# E-08_eMMC.net
KiCad netlist of a schematic drawn in Altium Designer
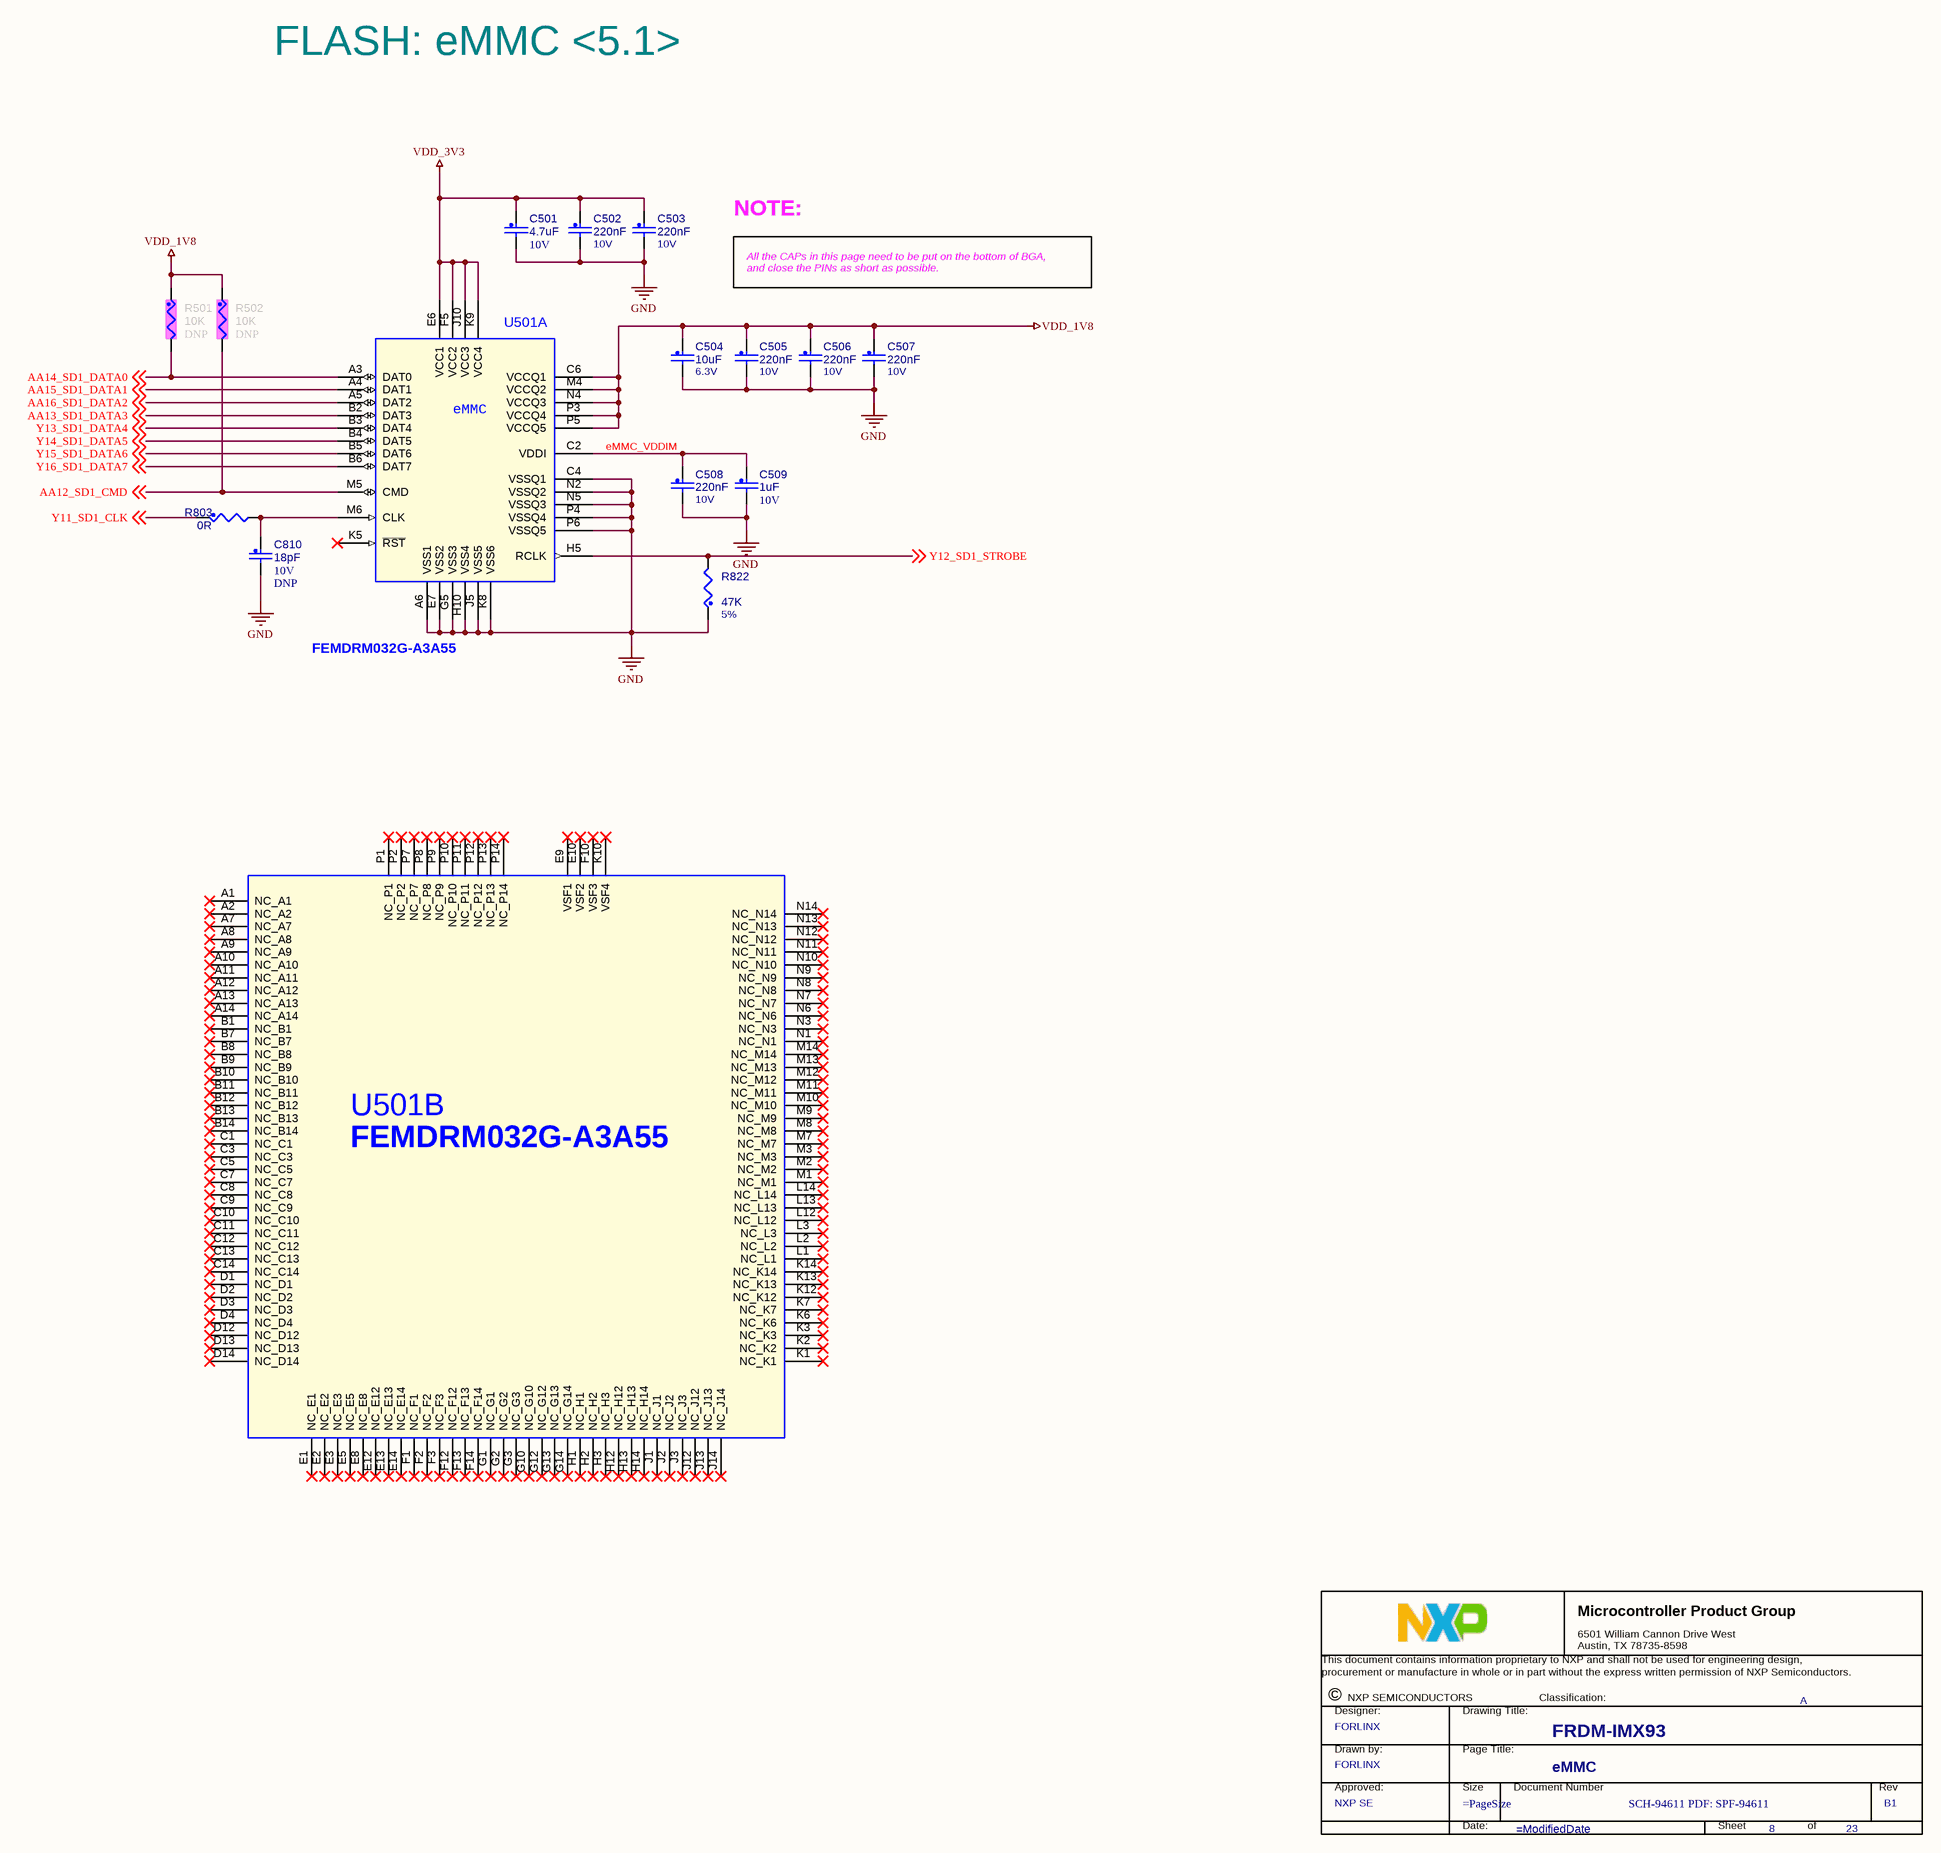
[diagram p0: E-08 eMMC.SchDoc]

(export (version "E")
  (design (tool "Eeschema 10.0.6"))
  (components
    (comp (ref "C501")
      (value "4.7uF")
      (footprint "C0402")
      (description "0402,4.7uF,10V,+/-10%,X5R")
      (fields (field (name "VOLTAGE") "10V") (field (name "TOLERANCE") "10%"))
      (libsource (lib "*") (part "CAP_NP"))
    )
    (comp (ref "C502")
      (value "220nF")
      (footprint "C0201")
      (description "0201,220nF,6.3V,+/-20%,X5R")
      (fields (field (name "TOLERANCE") "20%") (field (name "VOLTAGE") "10V"))
      (libsource (lib "*") (part "CAP_NP"))
    )
    (comp (ref "C503")
      (value "220nF")
      (footprint "C0201")
      (description "0201,220nF,6.3V,+/-20%,X5R")
      (fields (field (name "VOLTAGE") "10V") (field (name "TOLERANCE") "20%"))
      (libsource (lib "*") (part "CAP_NP"))
    )
    (comp (ref "C504")
      (value "10uF")
      (footprint "C0402")
      (description "0402,10uF,6.3V,+/-20%,X5R")
      (fields (field (name "VOLTAGE") "6.3V") (field (name "TOLERANCE") "20%"))
      (libsource (lib "*") (part "CAP_NP"))
    )
    (comp (ref "C505")
      (value "220nF")
      (footprint "C0201")
      (description "0201,220nF,6.3V,+/-20%,X5R")
      (fields (field (name "VOLTAGE") "10V") (field (name "TOLERANCE") "20%"))
      (libsource (lib "*") (part "CAP_NP"))
    )
    (comp (ref "C506")
      (value "220nF")
      (footprint "C0201")
      (description "0201,220nF,6.3V,+/-20%,X5R")
      (fields (field (name "VOLTAGE") "10V") (field (name "TOLERANCE") "20%"))
      (libsource (lib "*") (part "CAP_NP"))
    )
    (comp (ref "C507")
      (value "220nF")
      (footprint "C0201")
      (description "0201,220nF,6.3V,+/-20%,X5R")
      (fields (field (name "TOLERANCE") "20%") (field (name "VOLTAGE") "10V"))
      (libsource (lib "*") (part "CAP_NP"))
    )
    (comp (ref "C508")
      (value "220nF")
      (footprint "C0201")
      (description "0201,220nF,6.3V,+/-20%,X5R")
      (fields (field (name "TOLERANCE") "20%") (field (name "VOLTAGE") "10V"))
      (libsource (lib "*") (part "CAP_NP"))
    )
    (comp (ref "C509")
      (value "1uF")
      (footprint "C0201")
      (description "0201,1uF,10V,+/-20%,X5R")
      (fields (field (name "VOLTAGE") "10V") (field (name "TOLERANCE") "10%"))
      (libsource (lib "*") (part "CAP_NP"))
    )
    (comp (ref "C810")
      (value "18pF")
      (footprint "C0201")
      (description "0201,18pF,50V,+/-5%,NPO")
      (fields (field (name "ASSY_OPT") "DNP") (field (name "VOLTAGE") "10V") (field (name "TOLERANCE") "10%"))
      (libsource (lib "*") (part "CAP_NP"))
    )
    (comp (ref "R501")
      (value "10K")
      (footprint "R0201")
      (description "0201,10K,+/-5%")
      (fields (field (name "ASSY_OPT") "DNP") (field (name "TOLERANCE") "5%"))
      (libsource (lib "*") (part "RES"))
    )
    (comp (ref "R502")
      (value "10K")
      (footprint "R0201")
      (description "0201,10K,+/-5%")
      (fields (field (name "ASSY_OPT") "DNP") (field (name "TOLERANCE") "5%"))
      (libsource (lib "*") (part "RES"))
    )
    (comp (ref "R803")
      (value "0R")
      (footprint "R0201")
      (description "0201,0Ohm,+/-5%")
      (fields (field (name "TOLERANCE") "5%"))
      (libsource (lib "*") (part "RES"))
    )
    (comp (ref "R822")
      (value "47K")
      (footprint "R0201")
      (description "0201,47K,5%")
      (fields (field (name "TOLERANCE") "5%") (field (name "VOLTAGE") "25V"))
      (libsource (lib "*") (part "RES"))
    )
    (comp (ref "U501")
      (value "FEMDRM032G-A3A55")
      (footprint "fbga153_0p5_11p5x13")
      (description "FEMDRM032G-A3A55,153FBGA,eMMC5.1,32GB,-25~85+C")
      (libsource (lib "*") (part "SDINBDA6_32G_I_VFBGA_153P"))
    )
  )
  (nets
    (net (code "1") (name "/eMMC_VDDIM") (class "Default")
      (node (ref "C508") (pin "1") (pinfunction "1_1") (pintype "passive"))
      (node (ref "C509") (pin "1") (pinfunction "1_1") (pintype "passive"))
      (node (ref "U501") (pin "C2") (pinfunction "VDDI_C2") (pintype "power_in"))
    )
    (net (code "2") (name "AA12_SD1_CMD") (class "Default")
      (node (ref "R502") (pin "2") (pinfunction "2_2") (pintype "passive"))
      (node (ref "U501") (pin "M5") (pinfunction "CMD_M5") (pintype "bidirectional"))
    )
    (net (code "3") (name "AA13_SD1_DATA3") (class "Default")
      (node (ref "U501") (pin "B2") (pinfunction "DAT3_B2") (pintype "bidirectional"))
    )
    (net (code "4") (name "AA14_SD1_DATA0") (class "Default")
      (node (ref "R501") (pin "2") (pinfunction "2_2") (pintype "passive"))
      (node (ref "U501") (pin "A3") (pinfunction "DAT0_A3") (pintype "bidirectional"))
    )
    (net (code "5") (name "AA15_SD1_DATA1") (class "Default")
      (node (ref "U501") (pin "A4") (pinfunction "DAT1_A4") (pintype "bidirectional"))
    )
    (net (code "6") (name "AA16_SD1_DATA2") (class "Default")
      (node (ref "U501") (pin "A5") (pinfunction "DAT2_A5") (pintype "bidirectional"))
    )
    (net (code "7") (name "GND") (class "Default")
      (node (ref "C501") (pin "2") (pinfunction "2_2") (pintype "passive"))
      (node (ref "C502") (pin "2") (pinfunction "2_2") (pintype "passive"))
      (node (ref "C503") (pin "2") (pinfunction "2_2") (pintype "passive"))
      (node (ref "C504") (pin "2") (pinfunction "2_2") (pintype "passive"))
      (node (ref "C505") (pin "2") (pinfunction "2_2") (pintype "passive"))
      (node (ref "C506") (pin "2") (pinfunction "2_2") (pintype "passive"))
      (node (ref "C507") (pin "2") (pinfunction "2_2") (pintype "passive"))
      (node (ref "C508") (pin "2") (pinfunction "2_2") (pintype "passive"))
      (node (ref "C509") (pin "2") (pinfunction "2_2") (pintype "passive"))
      (node (ref "C810") (pin "2") (pinfunction "2_2") (pintype "passive"))
      (node (ref "R822") (pin "1") (pinfunction "1_1") (pintype "passive"))
      (node (ref "U501") (pin "A6") (pinfunction "VSS1_A6") (pintype "power_in"))
      (node (ref "U501") (pin "C4") (pinfunction "VSSQ1_C4") (pintype "power_in"))
      (node (ref "U501") (pin "E7") (pinfunction "VSS2_E7") (pintype "power_in"))
      (node (ref "U501") (pin "G5") (pinfunction "VSS3_G5") (pintype "power_in"))
      (node (ref "U501") (pin "H10") (pinfunction "VSS4_H10") (pintype "power_in"))
      (node (ref "U501") (pin "J5") (pinfunction "VSS5_J5") (pintype "power_in"))
      (node (ref "U501") (pin "K8") (pinfunction "VSS6_K8") (pintype "power_in"))
      (node (ref "U501") (pin "N2") (pinfunction "VSSQ2_N2") (pintype "power_in"))
      (node (ref "U501") (pin "N5") (pinfunction "VSSQ3_N5") (pintype "power_in"))
      (node (ref "U501") (pin "P4") (pinfunction "VSSQ4_P4") (pintype "power_in"))
      (node (ref "U501") (pin "P6") (pinfunction "VSSQ5_P6") (pintype "power_in"))
    )
    (net (code "8") (name "Net-(U501A-CLK)") (class "Default")
      (node (ref "C810") (pin "1") (pinfunction "1_1") (pintype "passive"))
      (node (ref "R803") (pin "2") (pinfunction "2_2") (pintype "passive"))
      (node (ref "U501") (pin "M6") (pinfunction "CLK_M6") (pintype "input"))
    )
    (net (code "9") (name "VDD_1V8") (class "Default")
      (node (ref "C504") (pin "1") (pinfunction "1_1") (pintype "passive"))
      (node (ref "C505") (pin "1") (pinfunction "1_1") (pintype "passive"))
      (node (ref "C506") (pin "1") (pinfunction "1_1") (pintype "passive"))
      (node (ref "C507") (pin "1") (pinfunction "1_1") (pintype "passive"))
      (node (ref "R501") (pin "1") (pinfunction "1_1") (pintype "passive"))
      (node (ref "R502") (pin "1") (pinfunction "1_1") (pintype "passive"))
      (node (ref "U501") (pin "C6") (pinfunction "VCCQ1_C6") (pintype "power_in"))
      (node (ref "U501") (pin "M4") (pinfunction "VCCQ2_M4") (pintype "power_in"))
      (node (ref "U501") (pin "N4") (pinfunction "VCCQ3_N4") (pintype "power_in"))
      (node (ref "U501") (pin "P3") (pinfunction "VCCQ4_P3") (pintype "power_in"))
      (node (ref "U501") (pin "P5") (pinfunction "VCCQ5_P5") (pintype "power_in"))
    )
    (net (code "10") (name "VDD_3V3") (class "Default")
      (node (ref "C501") (pin "1") (pinfunction "1_1") (pintype "passive"))
      (node (ref "C502") (pin "1") (pinfunction "1_1") (pintype "passive"))
      (node (ref "C503") (pin "1") (pinfunction "1_1") (pintype "passive"))
      (node (ref "U501") (pin "E6") (pinfunction "VCC1_E6") (pintype "power_in"))
      (node (ref "U501") (pin "F5") (pinfunction "VCC2_F5") (pintype "power_in"))
      (node (ref "U501") (pin "J10") (pinfunction "VCC3_J10") (pintype "power_in"))
      (node (ref "U501") (pin "K9") (pinfunction "VCC4_K9") (pintype "power_in"))
    )
    (net (code "11") (name "Y11_SD1_CLK") (class "Default")
      (node (ref "R803") (pin "1") (pinfunction "1_1") (pintype "passive"))
    )
    (net (code "12") (name "Y12_SD1_STROBE") (class "Default")
      (node (ref "R822") (pin "2") (pinfunction "2_2") (pintype "passive"))
      (node (ref "U501") (pin "H5") (pinfunction "RCLK_H5") (pintype "output"))
    )
    (net (code "13") (name "Y13_SD1_DATA4") (class "Default")
      (node (ref "U501") (pin "B3") (pinfunction "DAT4_B3") (pintype "bidirectional"))
    )
    (net (code "14") (name "Y14_SD1_DATA5") (class "Default")
      (node (ref "U501") (pin "B4") (pinfunction "DAT5_B4") (pintype "bidirectional"))
    )
    (net (code "15") (name "Y15_SD1_DATA6") (class "Default")
      (node (ref "U501") (pin "B5") (pinfunction "DAT6_B5") (pintype "bidirectional"))
    )
    (net (code "16") (name "Y16_SD1_DATA7") (class "Default")
      (node (ref "U501") (pin "B6") (pinfunction "DAT7_B6") (pintype "bidirectional"))
    )
    (net (code "17") (name "unconnected-(U501A-~{RST}-PadK5)") (class "Default")
      (node (ref "U501") (pin "K5") (pinfunction "~{RST}_K5") (pintype "input+no_connect"))
    )
    (net (code "18") (name "unconnected-(U501B-NC_A1-PadA1)") (class "Default")
      (node (ref "U501") (pin "A1") (pinfunction "NC_A1_A1") (pintype "passive+no_connect"))
    )
    (net (code "19") (name "unconnected-(U501B-NC_A2-PadA2)") (class "Default")
      (node (ref "U501") (pin "A2") (pinfunction "NC_A2_A2") (pintype "passive+no_connect"))
    )
    (net (code "20") (name "unconnected-(U501B-NC_A7-PadA7)") (class "Default")
      (node (ref "U501") (pin "A7") (pinfunction "NC_A7_A7") (pintype "passive+no_connect"))
    )
    (net (code "21") (name "unconnected-(U501B-NC_A8-PadA8)") (class "Default")
      (node (ref "U501") (pin "A8") (pinfunction "NC_A8_A8") (pintype "passive+no_connect"))
    )
    (net (code "22") (name "unconnected-(U501B-NC_A9-PadA9)") (class "Default")
      (node (ref "U501") (pin "A9") (pinfunction "NC_A9_A9") (pintype "passive+no_connect"))
    )
    (net (code "23") (name "unconnected-(U501B-NC_A10-PadA10)") (class "Default")
      (node (ref "U501") (pin "A10") (pinfunction "NC_A10_A10") (pintype "passive+no_connect"))
    )
    (net (code "24") (name "unconnected-(U501B-NC_A11-PadA11)") (class "Default")
      (node (ref "U501") (pin "A11") (pinfunction "NC_A11_A11") (pintype "passive+no_connect"))
    )
    (net (code "25") (name "unconnected-(U501B-NC_A12-PadA12)") (class "Default")
      (node (ref "U501") (pin "A12") (pinfunction "NC_A12_A12") (pintype "passive+no_connect"))
    )
    (net (code "26") (name "unconnected-(U501B-NC_A13-PadA13)") (class "Default")
      (node (ref "U501") (pin "A13") (pinfunction "NC_A13_A13") (pintype "passive+no_connect"))
    )
    (net (code "27") (name "unconnected-(U501B-NC_A14-PadA14)") (class "Default")
      (node (ref "U501") (pin "A14") (pinfunction "NC_A14_A14") (pintype "passive+no_connect"))
    )
    (net (code "28") (name "unconnected-(U501B-NC_B1-PadB1)") (class "Default")
      (node (ref "U501") (pin "B1") (pinfunction "NC_B1_B1") (pintype "passive+no_connect"))
    )
    (net (code "29") (name "unconnected-(U501B-NC_B7-PadB7)") (class "Default")
      (node (ref "U501") (pin "B7") (pinfunction "NC_B7_B7") (pintype "passive+no_connect"))
    )
    (net (code "30") (name "unconnected-(U501B-NC_B8-PadB8)") (class "Default")
      (node (ref "U501") (pin "B8") (pinfunction "NC_B8_B8") (pintype "passive+no_connect"))
    )
    (net (code "31") (name "unconnected-(U501B-NC_B9-PadB9)") (class "Default")
      (node (ref "U501") (pin "B9") (pinfunction "NC_B9_B9") (pintype "passive+no_connect"))
    )
    (net (code "32") (name "unconnected-(U501B-NC_B10-PadB10)") (class "Default")
      (node (ref "U501") (pin "B10") (pinfunction "NC_B10_B10") (pintype "passive+no_connect"))
    )
    (net (code "33") (name "unconnected-(U501B-NC_B11-PadB11)") (class "Default")
      (node (ref "U501") (pin "B11") (pinfunction "NC_B11_B11") (pintype "passive+no_connect"))
    )
    (net (code "34") (name "unconnected-(U501B-NC_B12-PadB12)") (class "Default")
      (node (ref "U501") (pin "B12") (pinfunction "NC_B12_B12") (pintype "passive+no_connect"))
    )
    (net (code "35") (name "unconnected-(U501B-NC_B13-PadB13)") (class "Default")
      (node (ref "U501") (pin "B13") (pinfunction "NC_B13_B13") (pintype "passive+no_connect"))
    )
    (net (code "36") (name "unconnected-(U501B-NC_B14-PadB14)") (class "Default")
      (node (ref "U501") (pin "B14") (pinfunction "NC_B14_B14") (pintype "passive+no_connect"))
    )
    (net (code "37") (name "unconnected-(U501B-NC_C1-PadC1)") (class "Default")
      (node (ref "U501") (pin "C1") (pinfunction "NC_C1_C1") (pintype "passive+no_connect"))
    )
    (net (code "38") (name "unconnected-(U501B-NC_C3-PadC3)") (class "Default")
      (node (ref "U501") (pin "C3") (pinfunction "NC_C3_C3") (pintype "passive+no_connect"))
    )
    (net (code "39") (name "unconnected-(U501B-NC_C5-PadC5)") (class "Default")
      (node (ref "U501") (pin "C5") (pinfunction "NC_C5_C5") (pintype "passive+no_connect"))
    )
    (net (code "40") (name "unconnected-(U501B-NC_C7-PadC7)") (class "Default")
      (node (ref "U501") (pin "C7") (pinfunction "NC_C7_C7") (pintype "passive+no_connect"))
    )
    (net (code "41") (name "unconnected-(U501B-NC_C8-PadC8)") (class "Default")
      (node (ref "U501") (pin "C8") (pinfunction "NC_C8_C8") (pintype "passive+no_connect"))
    )
    (net (code "42") (name "unconnected-(U501B-NC_C9-PadC9)") (class "Default")
      (node (ref "U501") (pin "C9") (pinfunction "NC_C9_C9") (pintype "passive+no_connect"))
    )
    (net (code "43") (name "unconnected-(U501B-NC_C10-PadC10)") (class "Default")
      (node (ref "U501") (pin "C10") (pinfunction "NC_C10_C10") (pintype "passive+no_connect"))
    )
    (net (code "44") (name "unconnected-(U501B-NC_C11-PadC11)") (class "Default")
      (node (ref "U501") (pin "C11") (pinfunction "NC_C11_C11") (pintype "passive+no_connect"))
    )
    (net (code "45") (name "unconnected-(U501B-NC_C12-PadC12)") (class "Default")
      (node (ref "U501") (pin "C12") (pinfunction "NC_C12_C12") (pintype "passive+no_connect"))
    )
    (net (code "46") (name "unconnected-(U501B-NC_C13-PadC13)") (class "Default")
      (node (ref "U501") (pin "C13") (pinfunction "NC_C13_C13") (pintype "passive+no_connect"))
    )
    (net (code "47") (name "unconnected-(U501B-NC_C14-PadC14)") (class "Default")
      (node (ref "U501") (pin "C14") (pinfunction "NC_C14_C14") (pintype "passive+no_connect"))
    )
    (net (code "48") (name "unconnected-(U501B-NC_D1-PadD1)") (class "Default")
      (node (ref "U501") (pin "D1") (pinfunction "NC_D1_D1") (pintype "passive+no_connect"))
    )
    (net (code "49") (name "unconnected-(U501B-NC_D2-PadD2)") (class "Default")
      (node (ref "U501") (pin "D2") (pinfunction "NC_D2_D2") (pintype "passive+no_connect"))
    )
    (net (code "50") (name "unconnected-(U501B-NC_D3-PadD3)") (class "Default")
      (node (ref "U501") (pin "D3") (pinfunction "NC_D3_D3") (pintype "passive+no_connect"))
    )
    (net (code "51") (name "unconnected-(U501B-NC_D4-PadD4)") (class "Default")
      (node (ref "U501") (pin "D4") (pinfunction "NC_D4_D4") (pintype "passive+no_connect"))
    )
    (net (code "52") (name "unconnected-(U501B-NC_D12-PadD12)") (class "Default")
      (node (ref "U501") (pin "D12") (pinfunction "NC_D12_D12") (pintype "passive+no_connect"))
    )
    (net (code "53") (name "unconnected-(U501B-NC_D13-PadD13)") (class "Default")
      (node (ref "U501") (pin "D13") (pinfunction "NC_D13_D13") (pintype "passive+no_connect"))
    )
    (net (code "54") (name "unconnected-(U501B-NC_D14-PadD14)") (class "Default")
      (node (ref "U501") (pin "D14") (pinfunction "NC_D14_D14") (pintype "passive+no_connect"))
    )
    (net (code "55") (name "unconnected-(U501B-NC_E1-PadE1)") (class "Default")
      (node (ref "U501") (pin "E1") (pinfunction "NC_E1_E1") (pintype "passive+no_connect"))
    )
    (net (code "56") (name "unconnected-(U501B-NC_E2-PadE2)") (class "Default")
      (node (ref "U501") (pin "E2") (pinfunction "NC_E2_E2") (pintype "passive+no_connect"))
    )
    (net (code "57") (name "unconnected-(U501B-NC_E3-PadE3)") (class "Default")
      (node (ref "U501") (pin "E3") (pinfunction "NC_E3_E3") (pintype "passive+no_connect"))
    )
    (net (code "58") (name "unconnected-(U501B-NC_E5-PadE5)") (class "Default")
      (node (ref "U501") (pin "E5") (pinfunction "NC_E5_E5") (pintype "passive+no_connect"))
    )
    (net (code "59") (name "unconnected-(U501B-NC_E8-PadE8)") (class "Default")
      (node (ref "U501") (pin "E8") (pinfunction "NC_E8_E8") (pintype "passive+no_connect"))
    )
    (net (code "60") (name "unconnected-(U501B-NC_E12-PadE12)") (class "Default")
      (node (ref "U501") (pin "E12") (pinfunction "NC_E12_E12") (pintype "passive+no_connect"))
    )
    (net (code "61") (name "unconnected-(U501B-NC_E13-PadE13)") (class "Default")
      (node (ref "U501") (pin "E13") (pinfunction "NC_E13_E13") (pintype "passive+no_connect"))
    )
    (net (code "62") (name "unconnected-(U501B-NC_E14-PadE14)") (class "Default")
      (node (ref "U501") (pin "E14") (pinfunction "NC_E14_E14") (pintype "passive+no_connect"))
    )
    (net (code "63") (name "unconnected-(U501B-NC_F1-PadF1)") (class "Default")
      (node (ref "U501") (pin "F1") (pinfunction "NC_F1_F1") (pintype "passive+no_connect"))
    )
    (net (code "64") (name "unconnected-(U501B-NC_F2-PadF2)") (class "Default")
      (node (ref "U501") (pin "F2") (pinfunction "NC_F2_F2") (pintype "passive+no_connect"))
    )
    (net (code "65") (name "unconnected-(U501B-NC_F3-PadF3)") (class "Default")
      (node (ref "U501") (pin "F3") (pinfunction "NC_F3_F3") (pintype "passive+no_connect"))
    )
    (net (code "66") (name "unconnected-(U501B-NC_F12-PadF12)") (class "Default")
      (node (ref "U501") (pin "F12") (pinfunction "NC_F12_F12") (pintype "passive+no_connect"))
    )
    (net (code "67") (name "unconnected-(U501B-NC_F13-PadF13)") (class "Default")
      (node (ref "U501") (pin "F13") (pinfunction "NC_F13_F13") (pintype "passive+no_connect"))
    )
    (net (code "68") (name "unconnected-(U501B-NC_F14-PadF14)") (class "Default")
      (node (ref "U501") (pin "F14") (pinfunction "NC_F14_F14") (pintype "passive+no_connect"))
    )
    (net (code "69") (name "unconnected-(U501B-NC_G1-PadG1)") (class "Default")
      (node (ref "U501") (pin "G1") (pinfunction "NC_G1_G1") (pintype "passive+no_connect"))
    )
    (net (code "70") (name "unconnected-(U501B-NC_G2-PadG2)") (class "Default")
      (node (ref "U501") (pin "G2") (pinfunction "NC_G2_G2") (pintype "passive+no_connect"))
    )
    (net (code "71") (name "unconnected-(U501B-NC_G3-PadG3)") (class "Default")
      (node (ref "U501") (pin "G3") (pinfunction "NC_G3_G3") (pintype "passive+no_connect"))
    )
    (net (code "72") (name "unconnected-(U501B-NC_G10-PadG10)") (class "Default")
      (node (ref "U501") (pin "G10") (pinfunction "NC_G10_G10") (pintype "passive+no_connect"))
    )
    (net (code "73") (name "unconnected-(U501B-NC_G12-PadG12)") (class "Default")
      (node (ref "U501") (pin "G12") (pinfunction "NC_G12_G12") (pintype "passive+no_connect"))
    )
    (net (code "74") (name "unconnected-(U501B-NC_G13-PadG13)") (class "Default")
      (node (ref "U501") (pin "G13") (pinfunction "NC_G13_G13") (pintype "passive+no_connect"))
    )
    (net (code "75") (name "unconnected-(U501B-NC_G14-PadG14)") (class "Default")
      (node (ref "U501") (pin "G14") (pinfunction "NC_G14_G14") (pintype "passive+no_connect"))
    )
    (net (code "76") (name "unconnected-(U501B-NC_H1-PadH1)") (class "Default")
      (node (ref "U501") (pin "H1") (pinfunction "NC_H1_H1") (pintype "passive+no_connect"))
    )
    (net (code "77") (name "unconnected-(U501B-NC_H2-PadH2)") (class "Default")
      (node (ref "U501") (pin "H2") (pinfunction "NC_H2_H2") (pintype "passive+no_connect"))
    )
    (net (code "78") (name "unconnected-(U501B-NC_H3-PadH3)") (class "Default")
      (node (ref "U501") (pin "H3") (pinfunction "NC_H3_H3") (pintype "passive+no_connect"))
    )
    (net (code "79") (name "unconnected-(U501B-NC_H12-PadH12)") (class "Default")
      (node (ref "U501") (pin "H12") (pinfunction "NC_H12_H12") (pintype "passive+no_connect"))
    )
    (net (code "80") (name "unconnected-(U501B-NC_H13-PadH13)") (class "Default")
      (node (ref "U501") (pin "H13") (pinfunction "NC_H13_H13") (pintype "passive+no_connect"))
    )
    (net (code "81") (name "unconnected-(U501B-NC_H14-PadH14)") (class "Default")
      (node (ref "U501") (pin "H14") (pinfunction "NC_H14_H14") (pintype "passive+no_connect"))
    )
    (net (code "82") (name "unconnected-(U501B-NC_J1-PadJ1)") (class "Default")
      (node (ref "U501") (pin "J1") (pinfunction "NC_J1_J1") (pintype "passive+no_connect"))
    )
    (net (code "83") (name "unconnected-(U501B-NC_J2-PadJ2)") (class "Default")
      (node (ref "U501") (pin "J2") (pinfunction "NC_J2_J2") (pintype "passive+no_connect"))
    )
    (net (code "84") (name "unconnected-(U501B-NC_J3-PadJ3)") (class "Default")
      (node (ref "U501") (pin "J3") (pinfunction "NC_J3_J3") (pintype "passive+no_connect"))
    )
    (net (code "85") (name "unconnected-(U501B-NC_J12-PadJ12)") (class "Default")
      (node (ref "U501") (pin "J12") (pinfunction "NC_J12_J12") (pintype "passive+no_connect"))
    )
    (net (code "86") (name "unconnected-(U501B-NC_J13-PadJ13)") (class "Default")
      (node (ref "U501") (pin "J13") (pinfunction "NC_J13_J13") (pintype "passive+no_connect"))
    )
    (net (code "87") (name "unconnected-(U501B-NC_J14-PadJ14)") (class "Default")
      (node (ref "U501") (pin "J14") (pinfunction "NC_J14_J14") (pintype "passive+no_connect"))
    )
    (net (code "88") (name "unconnected-(U501B-NC_K1-PadK1)") (class "Default")
      (node (ref "U501") (pin "K1") (pinfunction "NC_K1_K1") (pintype "passive+no_connect"))
    )
    (net (code "89") (name "unconnected-(U501B-NC_K2-PadK2)") (class "Default")
      (node (ref "U501") (pin "K2") (pinfunction "NC_K2_K2") (pintype "passive+no_connect"))
    )
    (net (code "90") (name "unconnected-(U501B-NC_K3-PadK3)") (class "Default")
      (node (ref "U501") (pin "K3") (pinfunction "NC_K3_K3") (pintype "passive+no_connect"))
    )
    (net (code "91") (name "unconnected-(U501B-NC_K6-PadK6)") (class "Default")
      (node (ref "U501") (pin "K6") (pinfunction "NC_K6_K6") (pintype "passive+no_connect"))
    )
    (net (code "92") (name "unconnected-(U501B-NC_K7-PadK7)") (class "Default")
      (node (ref "U501") (pin "K7") (pinfunction "NC_K7_K7") (pintype "passive+no_connect"))
    )
    (net (code "93") (name "unconnected-(U501B-NC_K12-PadK12)") (class "Default")
      (node (ref "U501") (pin "K12") (pinfunction "NC_K12_K12") (pintype "passive+no_connect"))
    )
    (net (code "94") (name "unconnected-(U501B-NC_K13-PadK13)") (class "Default")
      (node (ref "U501") (pin "K13") (pinfunction "NC_K13_K13") (pintype "passive+no_connect"))
    )
    (net (code "95") (name "unconnected-(U501B-NC_K14-PadK14)") (class "Default")
      (node (ref "U501") (pin "K14") (pinfunction "NC_K14_K14") (pintype "passive+no_connect"))
    )
    (net (code "96") (name "unconnected-(U501B-NC_L1-PadL1)") (class "Default")
      (node (ref "U501") (pin "L1") (pinfunction "NC_L1_L1") (pintype "passive+no_connect"))
    )
    (net (code "97") (name "unconnected-(U501B-NC_L2-PadL2)") (class "Default")
      (node (ref "U501") (pin "L2") (pinfunction "NC_L2_L2") (pintype "passive+no_connect"))
    )
    (net (code "98") (name "unconnected-(U501B-NC_L3-PadL3)") (class "Default")
      (node (ref "U501") (pin "L3") (pinfunction "NC_L3_L3") (pintype "passive+no_connect"))
    )
    (net (code "99") (name "unconnected-(U501B-NC_L12-PadL12)") (class "Default")
      (node (ref "U501") (pin "L12") (pinfunction "NC_L12_L12") (pintype "passive+no_connect"))
    )
    (net (code "100") (name "unconnected-(U501B-NC_L13-PadL13)") (class "Default")
      (node (ref "U501") (pin "L13") (pinfunction "NC_L13_L13") (pintype "passive+no_connect"))
    )
    (net (code "101") (name "unconnected-(U501B-NC_L14-PadL14)") (class "Default")
      (node (ref "U501") (pin "L14") (pinfunction "NC_L14_L14") (pintype "passive+no_connect"))
    )
    (net (code "102") (name "unconnected-(U501B-NC_M1-PadM1)") (class "Default")
      (node (ref "U501") (pin "M1") (pinfunction "NC_M1_M1") (pintype "passive+no_connect"))
    )
    (net (code "103") (name "unconnected-(U501B-NC_M2-PadM2)") (class "Default")
      (node (ref "U501") (pin "M2") (pinfunction "NC_M2_M2") (pintype "passive+no_connect"))
    )
    (net (code "104") (name "unconnected-(U501B-NC_M3-PadM3)") (class "Default")
      (node (ref "U501") (pin "M3") (pinfunction "NC_M3_M3") (pintype "passive+no_connect"))
    )
    (net (code "105") (name "unconnected-(U501B-NC_M7-PadM7)") (class "Default")
      (node (ref "U501") (pin "M7") (pinfunction "NC_M7_M7") (pintype "passive+no_connect"))
    )
    (net (code "106") (name "unconnected-(U501B-NC_M8-PadM8)") (class "Default")
      (node (ref "U501") (pin "M8") (pinfunction "NC_M8_M8") (pintype "passive+no_connect"))
    )
    (net (code "107") (name "unconnected-(U501B-NC_M9-PadM9)") (class "Default")
      (node (ref "U501") (pin "M9") (pinfunction "NC_M9_M9") (pintype "passive+no_connect"))
    )
    (net (code "108") (name "unconnected-(U501B-NC_M10-PadM10)") (class "Default")
      (node (ref "U501") (pin "M10") (pinfunction "NC_M10_M10") (pintype "passive+no_connect"))
    )
    (net (code "109") (name "unconnected-(U501B-NC_M11-PadM11)") (class "Default")
      (node (ref "U501") (pin "M11") (pinfunction "NC_M11_M11") (pintype "passive+no_connect"))
    )
    (net (code "110") (name "unconnected-(U501B-NC_M12-PadM12)") (class "Default")
      (node (ref "U501") (pin "M12") (pinfunction "NC_M12_M12") (pintype "passive+no_connect"))
    )
    (net (code "111") (name "unconnected-(U501B-NC_M13-PadM13)") (class "Default")
      (node (ref "U501") (pin "M13") (pinfunction "NC_M13_M13") (pintype "passive+no_connect"))
    )
    (net (code "112") (name "unconnected-(U501B-NC_M14-PadM14)") (class "Default")
      (node (ref "U501") (pin "M14") (pinfunction "NC_M14_M14") (pintype "passive+no_connect"))
    )
    (net (code "113") (name "unconnected-(U501B-NC_N1-PadN1)") (class "Default")
      (node (ref "U501") (pin "N1") (pinfunction "NC_N1_N1") (pintype "passive+no_connect"))
    )
    (net (code "114") (name "unconnected-(U501B-NC_N3-PadN3)") (class "Default")
      (node (ref "U501") (pin "N3") (pinfunction "NC_N3_N3") (pintype "passive+no_connect"))
    )
    (net (code "115") (name "unconnected-(U501B-NC_N6-PadN6)") (class "Default")
      (node (ref "U501") (pin "N6") (pinfunction "NC_N6_N6") (pintype "passive+no_connect"))
    )
    (net (code "116") (name "unconnected-(U501B-NC_N7-PadN7)") (class "Default")
      (node (ref "U501") (pin "N7") (pinfunction "NC_N7_N7") (pintype "passive+no_connect"))
    )
    (net (code "117") (name "unconnected-(U501B-NC_N8-PadN8)") (class "Default")
      (node (ref "U501") (pin "N8") (pinfunction "NC_N8_N8") (pintype "passive+no_connect"))
    )
    (net (code "118") (name "unconnected-(U501B-NC_N9-PadN9)") (class "Default")
      (node (ref "U501") (pin "N9") (pinfunction "NC_N9_N9") (pintype "passive+no_connect"))
    )
    (net (code "119") (name "unconnected-(U501B-NC_N10-PadN10)") (class "Default")
      (node (ref "U501") (pin "N10") (pinfunction "NC_N10_N10") (pintype "passive+no_connect"))
    )
    (net (code "120") (name "unconnected-(U501B-NC_N11-PadN11)") (class "Default")
      (node (ref "U501") (pin "N11") (pinfunction "NC_N11_N11") (pintype "passive+no_connect"))
    )
    (net (code "121") (name "unconnected-(U501B-NC_N12-PadN12)") (class "Default")
      (node (ref "U501") (pin "N12") (pinfunction "NC_N12_N12") (pintype "passive+no_connect"))
    )
    (net (code "122") (name "unconnected-(U501B-NC_N13-PadN13)") (class "Default")
      (node (ref "U501") (pin "N13") (pinfunction "NC_N13_N13") (pintype "passive+no_connect"))
    )
    (net (code "123") (name "unconnected-(U501B-NC_N14-PadN14)") (class "Default")
      (node (ref "U501") (pin "N14") (pinfunction "NC_N14_N14") (pintype "passive+no_connect"))
    )
    (net (code "124") (name "unconnected-(U501B-NC_P1-PadP1)") (class "Default")
      (node (ref "U501") (pin "P1") (pinfunction "NC_P1_P1") (pintype "passive+no_connect"))
    )
    (net (code "125") (name "unconnected-(U501B-NC_P2-PadP2)") (class "Default")
      (node (ref "U501") (pin "P2") (pinfunction "NC_P2_P2") (pintype "passive+no_connect"))
    )
    (net (code "126") (name "unconnected-(U501B-NC_P7-PadP7)") (class "Default")
      (node (ref "U501") (pin "P7") (pinfunction "NC_P7_P7") (pintype "passive+no_connect"))
    )
    (net (code "127") (name "unconnected-(U501B-NC_P8-PadP8)") (class "Default")
      (node (ref "U501") (pin "P8") (pinfunction "NC_P8_P8") (pintype "passive+no_connect"))
    )
    (net (code "128") (name "unconnected-(U501B-NC_P9-PadP9)") (class "Default")
      (node (ref "U501") (pin "P9") (pinfunction "NC_P9_P9") (pintype "passive+no_connect"))
    )
    (net (code "129") (name "unconnected-(U501B-NC_P10-PadP10)") (class "Default")
      (node (ref "U501") (pin "P10") (pinfunction "NC_P10_P10") (pintype "passive+no_connect"))
    )
    (net (code "130") (name "unconnected-(U501B-NC_P11-PadP11)") (class "Default")
      (node (ref "U501") (pin "P11") (pinfunction "NC_P11_P11") (pintype "passive+no_connect"))
    )
    (net (code "131") (name "unconnected-(U501B-NC_P12-PadP12)") (class "Default")
      (node (ref "U501") (pin "P12") (pinfunction "NC_P12_P12") (pintype "passive+no_connect"))
    )
    (net (code "132") (name "unconnected-(U501B-NC_P13-PadP13)") (class "Default")
      (node (ref "U501") (pin "P13") (pinfunction "NC_P13_P13") (pintype "passive+no_connect"))
    )
    (net (code "133") (name "unconnected-(U501B-NC_P14-PadP14)") (class "Default")
      (node (ref "U501") (pin "P14") (pinfunction "NC_P14_P14") (pintype "passive+no_connect"))
    )
    (net (code "134") (name "unconnected-(U501B-VSF1-PadE9)") (class "Default")
      (node (ref "U501") (pin "E9") (pinfunction "VSF1_E9") (pintype "passive+no_connect"))
    )
    (net (code "135") (name "unconnected-(U501B-VSF2-PadE10)") (class "Default")
      (node (ref "U501") (pin "E10") (pinfunction "VSF2_E10") (pintype "passive+no_connect"))
    )
    (net (code "136") (name "unconnected-(U501B-VSF3-PadF10)") (class "Default")
      (node (ref "U501") (pin "F10") (pinfunction "VSF3_F10") (pintype "passive+no_connect"))
    )
    (net (code "137") (name "unconnected-(U501B-VSF4-PadK10)") (class "Default")
      (node (ref "U501") (pin "K10") (pinfunction "VSF4_K10") (pintype "passive+no_connect"))
    )
  )
)
